# SMA-Q2_replacement_board_v2_1.net
KiCad netlist of a schematic drawn in EAGLE
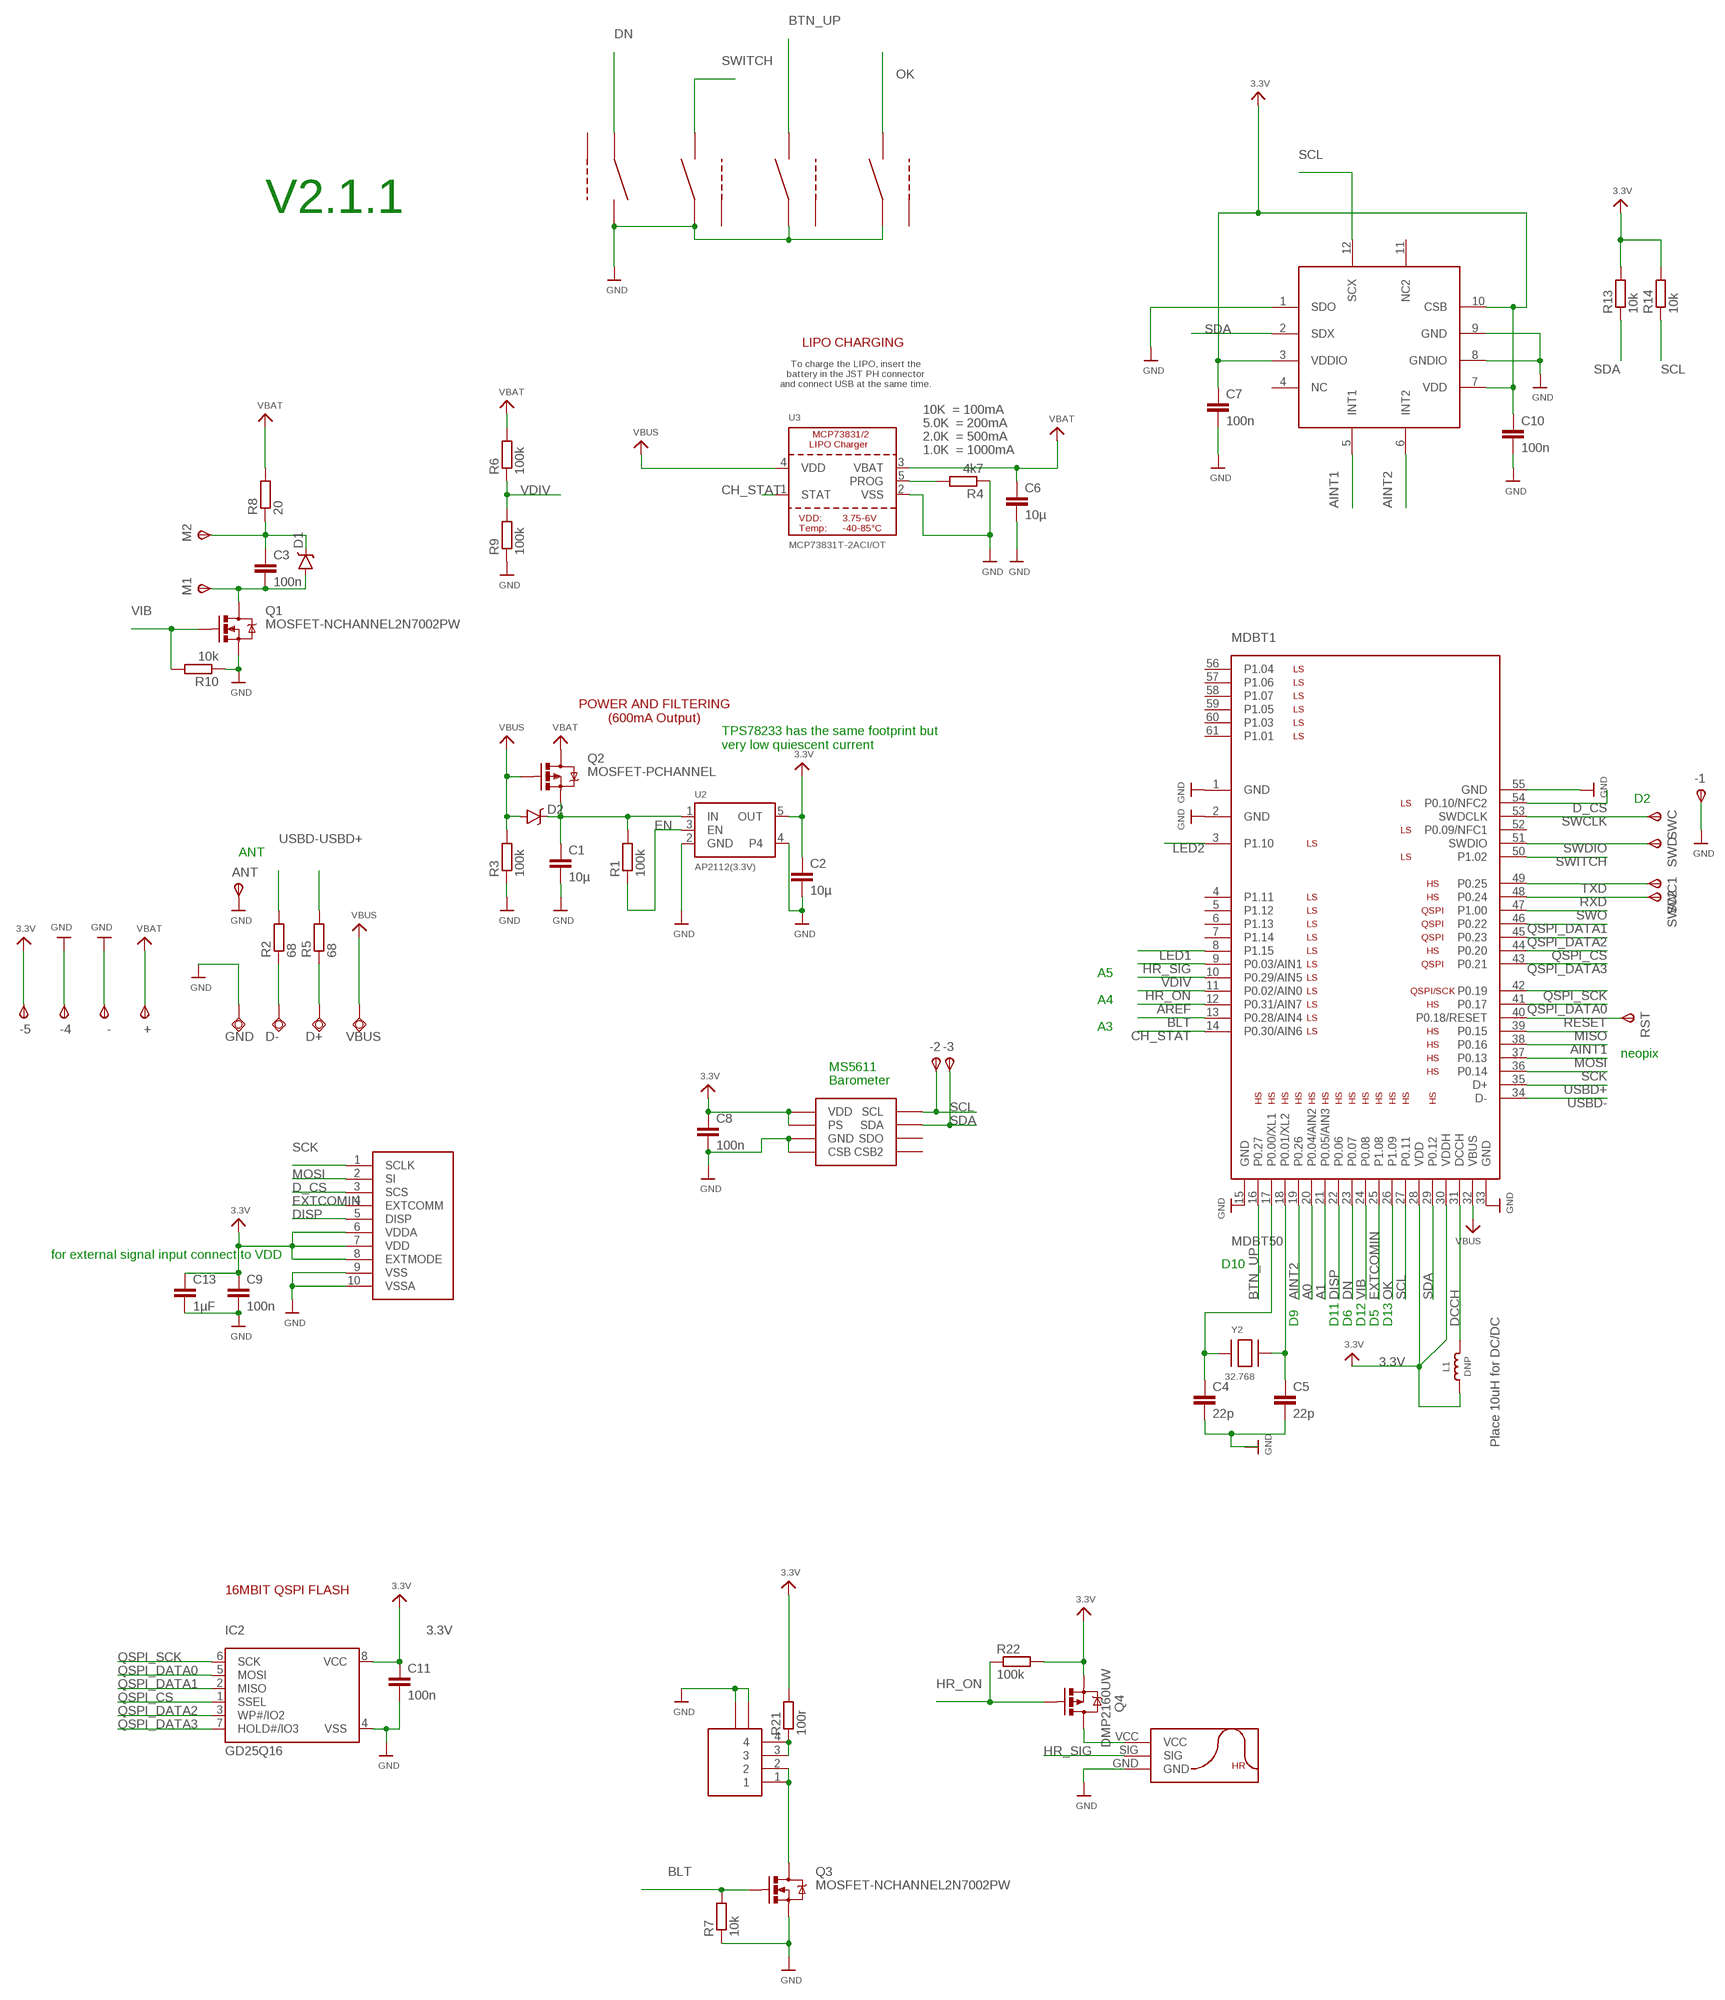
[diagram p0: schematic, sheet 1]

(export (version "E")
  (design (tool "Eeschema 10.0.6"))
  (components
    (comp (ref "+")
      (value "TPSTP09R")
      (footprint "eagle-import:TP09R")
      (libsource (lib "eagle-import") (part "TPSTP09R"))
    )
    (comp (ref "-")
      (value "TPSTP09R")
      (footprint "eagle-import:TP09R")
      (libsource (lib "eagle-import") (part "TPSTP09R"))
    )
    (comp (ref "-1")
      (value "TPSTP09R")
      (footprint "eagle-import:TP09R")
      (libsource (lib "eagle-import") (part "TPSTP09R"))
    )
    (comp (ref "-2")
      (value "TPSTP09R")
      (footprint "eagle-import:TP09R")
      (libsource (lib "eagle-import") (part "TPSTP09R"))
    )
    (comp (ref "-3")
      (value "TPSTP09R")
      (footprint "eagle-import:TP09R")
      (libsource (lib "eagle-import") (part "TPSTP09R"))
    )
    (comp (ref "-4")
      (value "TPSTP09R")
      (footprint "eagle-import:TP09R")
      (libsource (lib "eagle-import") (part "TPSTP09R"))
    )
    (comp (ref "-5")
      (value "TPSTP09R")
      (footprint "eagle-import:TP09R")
      (libsource (lib "eagle-import") (part "TPSTP09R"))
    )
    (comp (ref "ANT")
      (value "TPSTP19SQ")
      (footprint "eagle-import:TP19SQ")
      (libsource (lib "eagle-import") (part "TPSTP19SQ"))
    )
    (comp (ref "C1")
      (value "10µ")
      (footprint "eagle-import:C0603")
      (libsource (lib "eagle-import") (part "C-EUC0603"))
    )
    (comp (ref "C2")
      (value "10µ")
      (footprint "eagle-import:C0603")
      (libsource (lib "eagle-import") (part "C-EUC0603"))
    )
    (comp (ref "C3")
      (value "100n")
      (footprint "eagle-import:C0402")
      (libsource (lib "eagle-import") (part "C-EUC0402"))
    )
    (comp (ref "C4")
      (value "22p")
      (footprint "eagle-import:C0402")
      (libsource (lib "eagle-import") (part "C-EUC0402"))
    )
    (comp (ref "C5")
      (value "22p")
      (footprint "eagle-import:C0402")
      (libsource (lib "eagle-import") (part "C-EUC0402"))
    )
    (comp (ref "C6")
      (value "10µ")
      (footprint "eagle-import:C0603")
      (libsource (lib "eagle-import") (part "C-EUC0603"))
    )
    (comp (ref "C7")
      (value "100n")
      (footprint "eagle-import:C0402")
      (libsource (lib "eagle-import") (part "C-EUC0402"))
    )
    (comp (ref "C8")
      (value "100n")
      (footprint "eagle-import:C0402")
      (libsource (lib "eagle-import") (part "C-EUC0402"))
    )
    (comp (ref "C9")
      (value "100n")
      (footprint "eagle-import:C0402")
      (libsource (lib "eagle-import") (part "C-EUC0402"))
    )
    (comp (ref "C10")
      (value "100n")
      (footprint "eagle-import:C0402")
      (libsource (lib "eagle-import") (part "C-EUC0402"))
    )
    (comp (ref "C11")
      (value "100n")
      (footprint "eagle-import:C0402")
      (libsource (lib "eagle-import") (part "C-EUC0402"))
    )
    (comp (ref "C13")
      (value "1µF")
      (footprint "eagle-import:C0402")
      (libsource (lib "eagle-import") (part "C-EUC0402"))
    )
    (comp (ref "D+")
      (value "TPSQTP20R")
      (footprint "eagle-import:TP20R")
      (libsource (lib "eagle-import") (part "TPSQTP20R"))
    )
    (comp (ref "D-")
      (value "TPSQTP20R")
      (footprint "eagle-import:TP20R")
      (libsource (lib "eagle-import") (part "TPSQTP20R"))
    )
    (comp (ref "D1")
      (value "BAT20J")
      (footprint "eagle-import:SOD-323")
      (libsource (lib "eagle-import") (part "DIODE-SCHOTTKY-BAT20J"))
    )
    (comp (ref "D2")
      (value "BAT20J")
      (footprint "eagle-import:SOD-323")
      (libsource (lib "eagle-import") (part "DIODE-SCHOTTKY-BAT20J"))
    )
    (comp (ref "DWN")
      (value "LS12T2")
      (footprint "eagle-import:LS12T2")
      (libsource (lib "eagle-import") (part "LS12T2"))
    )
    (comp (ref "DWN1")
      (value "LS12T2")
      (footprint "eagle-import:LS12T2")
      (libsource (lib "eagle-import") (part "LS12T2"))
    )
    (comp (ref "DWN2")
      (value "LS12T2")
      (footprint "eagle-import:LS12T2")
      (libsource (lib "eagle-import") (part "LS12T2"))
    )
    (comp (ref "DWN3")
      (value "LS12T2")
      (footprint "eagle-import:LS12T2")
      (libsource (lib "eagle-import") (part "LS12T2"))
    )
    (comp (ref "GND")
      (value "TPSQTP20R")
      (footprint "eagle-import:TP20R")
      (libsource (lib "eagle-import") (part "TPSQTP20R"))
    )
    (comp (ref "IC2")
      (value "GD25Q16")
      (footprint "eagle-import:USON8")
      (libsource (lib "eagle-import") (part "SPIFLASH_8PINUX"))
    )
    (comp (ref "L1")
      (value "DNP")
      (footprint "eagle-import:_0805MP")
      (libsource (lib "eagle-import") (part "INDUCTOR_0805MP"))
    )
    (comp (ref "M1")
      (value "TPSTP09R")
      (footprint "eagle-import:TP09R")
      (libsource (lib "eagle-import") (part "TPSTP09R"))
    )
    (comp (ref "M2")
      (value "TPSTP09R")
      (footprint "eagle-import:TP09R")
      (libsource (lib "eagle-import") (part "TPSTP09R"))
    )
    (comp (ref "MDBT1")
      (value "MDBT50")
      (footprint "eagle-import:MDBT50")
      (libsource (lib "eagle-import") (part "MDBT50"))
    )
    (comp (ref "Q1")
      (value "MOSFET-NCHANNEL2N7002PW")
      (footprint "eagle-import:SOT323")
      (libsource (lib "eagle-import") (part "MOSFET-NCHANNEL2N7002PW"))
    )
    (comp (ref "Q2")
      (value "MOSFET-PCHANNEL")
      (footprint "eagle-import:SOT23-3")
      (libsource (lib "eagle-import") (part "MOSFET-PCHANNEL"))
    )
    (comp (ref "Q3")
      (value "MOSFET-NCHANNEL2N7002PW")
      (footprint "eagle-import:SOT323")
      (libsource (lib "eagle-import") (part "MOSFET-NCHANNEL2N7002PW"))
    )
    (comp (ref "Q4")
      (value "DMP2160UW")
      (footprint "eagle-import:SOT323")
      (libsource (lib "eagle-import") (part "MOSFET-P-CHANNEL-DMP2160UW"))
    )
    (comp (ref "R1")
      (value "100k")
      (footprint "eagle-import:R0402")
      (libsource (lib "eagle-import") (part "R-EU_R0402"))
    )
    (comp (ref "R2")
      (value "68")
      (footprint "eagle-import:R0402")
      (libsource (lib "eagle-import") (part "R-EU_R0402"))
    )
    (comp (ref "R3")
      (value "100k")
      (footprint "eagle-import:R0402")
      (libsource (lib "eagle-import") (part "R-EU_R0402"))
    )
    (comp (ref "R4")
      (value "4k7")
      (footprint "eagle-import:R0402")
      (libsource (lib "eagle-import") (part "R-EU_R0402"))
    )
    (comp (ref "R5")
      (value "68")
      (footprint "eagle-import:R0402")
      (libsource (lib "eagle-import") (part "R-EU_R0402"))
    )
    (comp (ref "R6")
      (value "100k")
      (footprint "eagle-import:R0402")
      (libsource (lib "eagle-import") (part "R-EU_R0402"))
    )
    (comp (ref "R7")
      (value "10k")
      (footprint "eagle-import:R0402")
      (libsource (lib "eagle-import") (part "R-EU_R0402"))
    )
    (comp (ref "R8")
      (value "20")
      (footprint "eagle-import:R0402")
      (libsource (lib "eagle-import") (part "R-EU_R0402"))
    )
    (comp (ref "R9")
      (value "100k")
      (footprint "eagle-import:R0402")
      (libsource (lib "eagle-import") (part "R-EU_R0402"))
    )
    (comp (ref "R10")
      (value "10k")
      (footprint "eagle-import:R0402")
      (libsource (lib "eagle-import") (part "R-EU_R0402"))
    )
    (comp (ref "R13")
      (value "10k")
      (footprint "eagle-import:R0402")
      (libsource (lib "eagle-import") (part "R-EU_R0402"))
    )
    (comp (ref "R14")
      (value "10k")
      (footprint "eagle-import:R0402")
      (libsource (lib "eagle-import") (part "R-EU_R0402"))
    )
    (comp (ref "R21")
      (value "100r")
      (footprint "eagle-import:R0402")
      (libsource (lib "eagle-import") (part "R-EU_R0402"))
    )
    (comp (ref "R22")
      (value "100k")
      (footprint "eagle-import:R0402")
      (libsource (lib "eagle-import") (part "R-EU_R0402"))
    )
    (comp (ref "RST")
      (value "TPSTP09R")
      (footprint "eagle-import:TP09R")
      (libsource (lib "eagle-import") (part "TPSTP09R"))
    )
    (comp (ref "SWC")
      (value "TPSTP09R")
      (footprint "eagle-import:TP09R")
      (libsource (lib "eagle-import") (part "TPSTP09R"))
    )
    (comp (ref "SWC1")
      (value "TPSTP09R")
      (footprint "eagle-import:TP09R")
      (libsource (lib "eagle-import") (part "TPSTP09R"))
    )
    (comp (ref "SWC2")
      (value "TPSTP09R")
      (footprint "eagle-import:TP09R")
      (libsource (lib "eagle-import") (part "TPSTP09R"))
    )
    (comp (ref "SWD")
      (value "TPSTP09R")
      (footprint "eagle-import:TP09R")
      (libsource (lib "eagle-import") (part "TPSTP09R"))
    )
    (comp (ref "U$2")
      (value "SHARP_MEM_DISP")
      (footprint "eagle-import:Y5BW")
      (libsource (lib "eagle-import") (part "SHARP_MEM_DISP"))
    )
    (comp (ref "U$6")
      (value "Y5B-4PIN")
      (footprint "eagle-import:Y5B-4PIN")
      (libsource (lib "eagle-import") (part "Y5B-4PIN"))
    )
    (comp (ref "U$7")
      (value "BMA400")
      (footprint "eagle-import:BMA400")
      (libsource (lib "eagle-import") (part "BMA400"))
    )
    (comp (ref "U$15")
      (value "MC5611")
      (footprint "eagle-import:MS5611")
      (libsource (lib "eagle-import") (part "MC5611"))
    )
    (comp (ref "U$45")
      (value "HR_PADS")
      (footprint "eagle-import:HR_PADS")
      (libsource (lib "eagle-import") (part "HR_PADS"))
    )
    (comp (ref "U2")
      (value "AP2112(3.3V)")
      (footprint "eagle-import:SOT23-5")
      (libsource (lib "eagle-import") (part "VREG_SOT23-5"))
    )
    (comp (ref "U3")
      (value "MCP73831T-2ACI/OT")
      (footprint "eagle-import:SOT23-5")
      (libsource (lib "eagle-import") (part "MCP73831/2"))
    )
    (comp (ref "VBUS")
      (value "TPSQTP20R")
      (footprint "eagle-import:TP20R")
      (libsource (lib "eagle-import") (part "TPSQTP20R"))
    )
    (comp (ref "Y2")
      (value "32.768")
      (footprint "eagle-import:XTAL3215")
      (libsource (lib "eagle-import") (part "XTAL-3.2X1.5"))
    )
  )
  (nets
    (net (code "1") (name "/A0") (class "Default")
      (node (ref "MDBT1") (pin "20") (pinfunction "P0.04/AIN2_20") (pintype "bidirectional"))
    )
    (net (code "2") (name "/A1") (class "Default")
      (node (ref "MDBT1") (pin "21") (pinfunction "P0.05/AIN3_21") (pintype "bidirectional"))
    )
    (net (code "3") (name "/AINT1") (class "Default")
      (node (ref "MDBT1") (pin "38") (pinfunction "P0.16_38") (pintype "bidirectional"))
      (node (ref "U$7") (pin "5") (pinfunction "INT1_5") (pintype "bidirectional"))
    )
    (net (code "4") (name "/AINT2") (class "Default")
      (node (ref "MDBT1") (pin "19") (pinfunction "P0.26_19") (pintype "bidirectional"))
      (node (ref "U$7") (pin "6") (pinfunction "INT2_6") (pintype "bidirectional"))
    )
    (net (code "5") (name "/AREF") (class "Default")
      (node (ref "MDBT1") (pin "12") (pinfunction "P0.31/AIN7_12") (pintype "bidirectional"))
    )
    (net (code "6") (name "/BLT") (class "Default")
      (node (ref "MDBT1") (pin "13") (pinfunction "P0.28/AIN4_13") (pintype "bidirectional"))
      (node (ref "Q3") (pin "1") (pinfunction "G_1") (pintype "passive"))
      (node (ref "R7") (pin "2") (pinfunction "2_2") (pintype "passive"))
    )
    (net (code "7") (name "/BTN_UP") (class "Default")
      (node (ref "DWN2") (pin "1") (pinfunction "1_1") (pintype "bidirectional"))
      (node (ref "MDBT1") (pin "16") (pinfunction "P0.27_16") (pintype "bidirectional"))
    )
    (net (code "8") (name "/CH_STAT") (class "Default")
      (node (ref "MDBT1") (pin "14") (pinfunction "P0.30/AIN6_14") (pintype "bidirectional"))
      (node (ref "U3") (pin "1") (pinfunction "STAT_1") (pintype "output"))
    )
    (net (code "9") (name "/DCCH") (class "Default")
      (node (ref "L1") (pin "2") (pinfunction "2_2") (pintype "passive"))
      (node (ref "MDBT1") (pin "31") (pinfunction "DCCH_31") (pintype "bidirectional"))
    )
    (net (code "10") (name "/DISP") (class "Default")
      (node (ref "MDBT1") (pin "22") (pinfunction "P0.06_22") (pintype "bidirectional"))
      (node (ref "U$2") (pin "5") (pinfunction "DISP_5") (pintype "bidirectional"))
    )
    (net (code "11") (name "/DN") (class "Default")
      (node (ref "DWN") (pin "2") (pinfunction "2_2") (pintype "bidirectional"))
      (node (ref "MDBT1") (pin "23") (pinfunction "P0.07_23") (pintype "bidirectional"))
    )
    (net (code "12") (name "/D_CS") (class "Default")
      (node (ref "MDBT1") (pin "54") (pinfunction "P0.10/NFC2_54") (pintype "bidirectional"))
      (node (ref "U$2") (pin "3") (pinfunction "SCS_3") (pintype "bidirectional"))
    )
    (net (code "13") (name "/EN") (class "Default")
      (node (ref "R1") (pin "1") (pinfunction "1_1") (pintype "passive"))
      (node (ref "U2") (pin "3") (pinfunction "EN_3") (pintype "input"))
    )
    (net (code "14") (name "/EXTCOMIN") (class "Default")
      (node (ref "MDBT1") (pin "25") (pinfunction "P1.08_25") (pintype "bidirectional"))
      (node (ref "U$2") (pin "4") (pinfunction "EXTCOMM_4") (pintype "bidirectional"))
    )
    (net (code "15") (name "/HR_ON") (class "Default")
      (node (ref "MDBT1") (pin "11") (pinfunction "P0.02/AIN0_11") (pintype "bidirectional"))
      (node (ref "Q4") (pin "1") (pinfunction "G_1") (pintype "passive"))
      (node (ref "R22") (pin "1") (pinfunction "1_1") (pintype "passive"))
    )
    (net (code "16") (name "/HR_SIG") (class "Default")
      (node (ref "MDBT1") (pin "9") (pinfunction "P0.03/AIN1_9") (pintype "bidirectional"))
      (node (ref "U$45") (pin "SIG") (pinfunction "SIG_SIG") (pintype "bidirectional"))
    )
    (net (code "17") (name "/LED1") (class "Default")
      (node (ref "MDBT1") (pin "8") (pinfunction "P1.15_8") (pintype "bidirectional"))
    )
    (net (code "18") (name "/LED2") (class "Default")
      (node (ref "MDBT1") (pin "3") (pinfunction "P1.10_3") (pintype "bidirectional"))
    )
    (net (code "19") (name "/MISO") (class "Default")
      (node (ref "MDBT1") (pin "39") (pinfunction "P0.15_39") (pintype "bidirectional"))
    )
    (net (code "20") (name "/MOSI") (class "Default")
      (node (ref "MDBT1") (pin "37") (pinfunction "P0.13_37") (pintype "bidirectional"))
      (node (ref "U$2") (pin "2") (pinfunction "SI_2") (pintype "bidirectional"))
    )
    (net (code "21") (name "/OK") (class "Default")
      (node (ref "DWN3") (pin "1") (pinfunction "1_1") (pintype "bidirectional"))
      (node (ref "MDBT1") (pin "26") (pinfunction "P1.09_26") (pintype "bidirectional"))
    )
    (net (code "22") (name "/QSPI_CS") (class "Default")
      (node (ref "IC2") (pin "1") (pinfunction "SSEL_1") (pintype "bidirectional"))
      (node (ref "MDBT1") (pin "44") (pinfunction "P0.20_44") (pintype "bidirectional"))
    )
    (net (code "23") (name "/QSPI_DATA0") (class "Default")
      (node (ref "IC2") (pin "5") (pinfunction "MOSI_5") (pintype "bidirectional"))
      (node (ref "MDBT1") (pin "41") (pinfunction "P0.17_41") (pintype "bidirectional"))
    )
    (net (code "24") (name "/QSPI_DATA1") (class "Default")
      (node (ref "IC2") (pin "2") (pinfunction "MISO_2") (pintype "bidirectional"))
      (node (ref "MDBT1") (pin "46") (pinfunction "P0.22_46") (pintype "bidirectional"))
    )
    (net (code "25") (name "/QSPI_DATA2") (class "Default")
      (node (ref "IC2") (pin "3") (pinfunction "WP#/IO2_3") (pintype "bidirectional"))
      (node (ref "MDBT1") (pin "45") (pinfunction "P0.23_45") (pintype "bidirectional"))
    )
    (net (code "26") (name "/QSPI_DATA3") (class "Default")
      (node (ref "IC2") (pin "7") (pinfunction "HOLD#/IO3_7") (pintype "bidirectional"))
      (node (ref "MDBT1") (pin "43") (pinfunction "P0.21_43") (pintype "bidirectional"))
    )
    (net (code "27") (name "/QSPI_SCK") (class "Default")
      (node (ref "IC2") (pin "6") (pinfunction "SCK_6") (pintype "bidirectional"))
      (node (ref "MDBT1") (pin "42") (pinfunction "P0.19_42") (pintype "bidirectional"))
    )
    (net (code "28") (name "/RESET") (class "Default")
      (node (ref "MDBT1") (pin "40") (pinfunction "P0.18/RESET_40") (pintype "bidirectional"))
      (node (ref "RST") (pin "TP") (pinfunction "PP_TP") (pintype "input"))
    )
    (net (code "29") (name "/RXD") (class "Default")
      (node (ref "MDBT1") (pin "48") (pinfunction "P0.24_48") (pintype "bidirectional"))
      (node (ref "SWC2") (pin "TP") (pinfunction "PP_TP") (pintype "input"))
    )
    (net (code "30") (name "/SCK") (class "Default")
      (node (ref "MDBT1") (pin "36") (pinfunction "P0.14_36") (pintype "bidirectional"))
      (node (ref "U$2") (pin "1") (pinfunction "SCLK_1") (pintype "bidirectional"))
    )
    (net (code "31") (name "/SCL") (class "Default")
      (node (ref "-2") (pin "TP") (pinfunction "PP_TP") (pintype "input"))
      (node (ref "MDBT1") (pin "27") (pinfunction "P0.11_27") (pintype "bidirectional"))
      (node (ref "R14") (pin "1") (pinfunction "1_1") (pintype "passive"))
      (node (ref "U$15") (pin "SCL") (pinfunction "SCL_SCL") (pintype "bidirectional"))
      (node (ref "U$7") (pin "12") (pinfunction "SCX_12") (pintype "bidirectional"))
    )
    (net (code "32") (name "/SDA") (class "Default")
      (node (ref "-3") (pin "TP") (pinfunction "PP_TP") (pintype "input"))
      (node (ref "MDBT1") (pin "29") (pinfunction "P0.12_29") (pintype "bidirectional"))
      (node (ref "R13") (pin "1") (pinfunction "1_1") (pintype "passive"))
      (node (ref "U$15") (pin "SDA") (pinfunction "SDA_SDA") (pintype "bidirectional"))
      (node (ref "U$7") (pin "2") (pinfunction "SDX_2") (pintype "bidirectional"))
    )
    (net (code "33") (name "/SWCLK") (class "Default")
      (node (ref "MDBT1") (pin "53") (pinfunction "SWDCLK_53") (pintype "bidirectional"))
      (node (ref "SWC") (pin "TP") (pinfunction "PP_TP") (pintype "input"))
    )
    (net (code "34") (name "/SWDIO") (class "Default")
      (node (ref "MDBT1") (pin "51") (pinfunction "SWDIO_51") (pintype "bidirectional"))
      (node (ref "SWD") (pin "TP") (pinfunction "PP_TP") (pintype "input"))
    )
    (net (code "35") (name "/SWITCH") (class "Default")
      (node (ref "DWN1") (pin "1") (pinfunction "1_1") (pintype "bidirectional"))
      (node (ref "MDBT1") (pin "50") (pinfunction "P1.02_50") (pintype "bidirectional"))
    )
    (net (code "36") (name "/SWO") (class "Default")
      (node (ref "MDBT1") (pin "47") (pinfunction "P1.00_47") (pintype "bidirectional"))
    )
    (net (code "37") (name "/TXD") (class "Default")
      (node (ref "MDBT1") (pin "49") (pinfunction "P0.25_49") (pintype "bidirectional"))
      (node (ref "SWC1") (pin "TP") (pinfunction "PP_TP") (pintype "input"))
    )
    (net (code "38") (name "/USBD+") (class "Default")
      (node (ref "MDBT1") (pin "35") (pinfunction "D+_35") (pintype "bidirectional"))
      (node (ref "R5") (pin "2") (pinfunction "2_2") (pintype "passive"))
    )
    (net (code "39") (name "/USBD-") (class "Default")
      (node (ref "MDBT1") (pin "34") (pinfunction "D-_34") (pintype "bidirectional"))
      (node (ref "R2") (pin "2") (pinfunction "2_2") (pintype "passive"))
    )
    (net (code "40") (name "/VDIV") (class "Default")
      (node (ref "MDBT1") (pin "10") (pinfunction "P0.29/AIN5_10") (pintype "bidirectional"))
      (node (ref "R6") (pin "1") (pinfunction "1_1") (pintype "passive"))
      (node (ref "R9") (pin "2") (pinfunction "2_2") (pintype "passive"))
    )
    (net (code "41") (name "/VIB") (class "Default")
      (node (ref "MDBT1") (pin "24") (pinfunction "P0.08_24") (pintype "bidirectional"))
      (node (ref "Q1") (pin "1") (pinfunction "G_1") (pintype "passive"))
      (node (ref "R10") (pin "2") (pinfunction "2_2") (pintype "passive"))
    )
    (net (code "42") (name "3.3V") (class "Default")
      (node (ref "-5") (pin "TP") (pinfunction "PP_TP") (pintype "input"))
      (node (ref "C10") (pin "1") (pinfunction "1_1") (pintype "passive"))
      (node (ref "C11") (pin "1") (pinfunction "1_1") (pintype "passive"))
      (node (ref "C13") (pin "1") (pinfunction "1_1") (pintype "passive"))
      (node (ref "C2") (pin "1") (pinfunction "1_1") (pintype "passive"))
      (node (ref "C7") (pin "1") (pinfunction "1_1") (pintype "passive"))
      (node (ref "C8") (pin "1") (pinfunction "1_1") (pintype "passive"))
      (node (ref "C9") (pin "1") (pinfunction "1_1") (pintype "passive"))
      (node (ref "IC2") (pin "8") (pinfunction "VCC_8") (pintype "bidirectional"))
      (node (ref "L1") (pin "1") (pinfunction "1_1") (pintype "passive"))
      (node (ref "MDBT1") (pin "28") (pinfunction "VDD_28") (pintype "bidirectional"))
      (node (ref "MDBT1") (pin "30") (pinfunction "VDDH_30") (pintype "bidirectional"))
      (node (ref "Q4") (pin "2") (pinfunction "S_2") (pintype "passive"))
      (node (ref "R13") (pin "2") (pinfunction "2_2") (pintype "passive"))
      (node (ref "R14") (pin "2") (pinfunction "2_2") (pintype "passive"))
      (node (ref "R21") (pin "2") (pinfunction "2_2") (pintype "passive"))
      (node (ref "R22") (pin "2") (pinfunction "2_2") (pintype "passive"))
      (node (ref "U$15") (pin "PS") (pinfunction "PS_PS") (pintype "bidirectional"))
      (node (ref "U$15") (pin "VDD") (pinfunction "VDD_VDD") (pintype "bidirectional"))
      (node (ref "U$2") (pin "6") (pinfunction "VDDA_6") (pintype "bidirectional"))
      (node (ref "U$2") (pin "7") (pinfunction "VDD_7") (pintype "bidirectional"))
      (node (ref "U$2") (pin "8") (pinfunction "EXTMODE_8") (pintype "bidirectional"))
      (node (ref "U$7") (pin "10") (pinfunction "CSB_10") (pintype "bidirectional"))
      (node (ref "U$7") (pin "3") (pinfunction "VDDIO_3") (pintype "bidirectional"))
      (node (ref "U$7") (pin "7") (pinfunction "VDD_7") (pintype "bidirectional"))
      (node (ref "U2") (pin "5") (pinfunction "OUT_5") (pintype "power_in"))
    )
    (net (code "43") (name "GND") (class "Default")
      (node (ref "-") (pin "TP") (pinfunction "PP_TP") (pintype "input"))
      (node (ref "-1") (pin "TP") (pinfunction "PP_TP") (pintype "input"))
      (node (ref "-4") (pin "TP") (pinfunction "PP_TP") (pintype "input"))
      (node (ref "ANT") (pin "TP") (pinfunction "PP_TP") (pintype "input"))
      (node (ref "C1") (pin "2") (pinfunction "2_2") (pintype "passive"))
      (node (ref "C10") (pin "2") (pinfunction "2_2") (pintype "passive"))
      (node (ref "C11") (pin "2") (pinfunction "2_2") (pintype "passive"))
      (node (ref "C13") (pin "2") (pinfunction "2_2") (pintype "passive"))
      (node (ref "C2") (pin "2") (pinfunction "2_2") (pintype "passive"))
      (node (ref "C4") (pin "2") (pinfunction "2_2") (pintype "passive"))
      (node (ref "C5") (pin "2") (pinfunction "2_2") (pintype "passive"))
      (node (ref "C6") (pin "2") (pinfunction "2_2") (pintype "passive"))
      (node (ref "C7") (pin "2") (pinfunction "2_2") (pintype "passive"))
      (node (ref "C8") (pin "2") (pinfunction "2_2") (pintype "passive"))
      (node (ref "C9") (pin "2") (pinfunction "2_2") (pintype "passive"))
      (node (ref "DWN") (pin "1") (pinfunction "1_1") (pintype "bidirectional"))
      (node (ref "DWN1") (pin "2") (pinfunction "2_2") (pintype "bidirectional"))
      (node (ref "DWN2") (pin "2") (pinfunction "2_2") (pintype "bidirectional"))
      (node (ref "DWN3") (pin "2") (pinfunction "2_2") (pintype "bidirectional"))
      (node (ref "GND") (pin "TP") (pinfunction "TP_TP") (pintype "input"))
      (node (ref "IC2") (pin "4") (pinfunction "VSS_4") (pintype "bidirectional"))
      (node (ref "MDBT1") (pin "1") (pinfunction "GND_1") (pintype "bidirectional"))
      (node (ref "MDBT1") (pin "15") (pinfunction "GND_15") (pintype "bidirectional"))
      (node (ref "MDBT1") (pin "2") (pinfunction "GND_2") (pintype "bidirectional"))
      (node (ref "MDBT1") (pin "33") (pinfunction "GND_33") (pintype "bidirectional"))
      (node (ref "MDBT1") (pin "55") (pinfunction "GND_55") (pintype "bidirectional"))
      (node (ref "Q1") (pin "2") (pinfunction "S_2") (pintype "passive"))
      (node (ref "Q3") (pin "2") (pinfunction "S_2") (pintype "passive"))
      (node (ref "R10") (pin "1") (pinfunction "1_1") (pintype "passive"))
      (node (ref "R3") (pin "1") (pinfunction "1_1") (pintype "passive"))
      (node (ref "R4") (pin "1") (pinfunction "1_1") (pintype "passive"))
      (node (ref "R7") (pin "1") (pinfunction "1_1") (pintype "passive"))
      (node (ref "R9") (pin "1") (pinfunction "1_1") (pintype "passive"))
      (node (ref "U$15") (pin "CSB") (pinfunction "CSB_CSB") (pintype "bidirectional"))
      (node (ref "U$15") (pin "GND") (pinfunction "GND_GND") (pintype "bidirectional"))
      (node (ref "U$2") (pin "10") (pinfunction "VSSA_10") (pintype "bidirectional"))
      (node (ref "U$2") (pin "9") (pinfunction "VSS_9") (pintype "bidirectional"))
      (node (ref "U$45") (pin "GND") (pinfunction "GND_GND") (pintype "bidirectional"))
      (node (ref "U$6") (pin "H1") (pinfunction "P$5_H1") (pintype "bidirectional"))
      (node (ref "U$6") (pin "H2") (pinfunction "P$6_H2") (pintype "bidirectional"))
      (node (ref "U$7") (pin "1") (pinfunction "SDO_1") (pintype "bidirectional"))
      (node (ref "U$7") (pin "8") (pinfunction "GNDIO_8") (pintype "bidirectional"))
      (node (ref "U$7") (pin "9") (pinfunction "GND_9") (pintype "bidirectional"))
      (node (ref "U2") (pin "2") (pinfunction "GND_2") (pintype "power_in"))
      (node (ref "U2") (pin "4") (pinfunction "P4_4") (pintype "bidirectional"))
      (node (ref "U3") (pin "2") (pinfunction "VSS_2") (pintype "power_in"))
    )
    (net (code "44") (name "Net-(D+-PadTP)") (class "Default")
      (node (ref "D+") (pin "TP") (pinfunction "TP_TP") (pintype "input"))
      (node (ref "R5") (pin "1") (pinfunction "1_1") (pintype "passive"))
    )
    (net (code "45") (name "Net-(D--PadTP)") (class "Default")
      (node (ref "D-") (pin "TP") (pinfunction "TP_TP") (pintype "input"))
      (node (ref "R2") (pin "1") (pinfunction "1_1") (pintype "passive"))
    )
    (net (code "46") (name "Net-(M1-PP)") (class "Default")
      (node (ref "C3") (pin "2") (pinfunction "2_2") (pintype "passive"))
      (node (ref "D1") (pin "A") (pinfunction "A_A") (pintype "passive"))
      (node (ref "M1") (pin "TP") (pinfunction "PP_TP") (pintype "input"))
      (node (ref "Q1") (pin "3") (pinfunction "D_3") (pintype "passive"))
    )
    (net (code "47") (name "Net-(M2-PP)") (class "Default")
      (node (ref "C3") (pin "1") (pinfunction "1_1") (pintype "passive"))
      (node (ref "D1") (pin "C") (pinfunction "C_C") (pintype "passive"))
      (node (ref "M2") (pin "TP") (pinfunction "PP_TP") (pintype "input"))
      (node (ref "R8") (pin "1") (pinfunction "1_1") (pintype "passive"))
    )
    (net (code "48") (name "Net-(MDBT1-P0.00{slash}XL1)") (class "Default")
      (node (ref "C4") (pin "1") (pinfunction "1_1") (pintype "passive"))
      (node (ref "MDBT1") (pin "17") (pinfunction "P0.00/XL1_17") (pintype "bidirectional"))
      (node (ref "Y2") (pin "P$1") (pinfunction "P$1_P$1") (pintype "bidirectional"))
    )
    (net (code "49") (name "Net-(MDBT1-P0.01{slash}XL2)") (class "Default")
      (node (ref "C5") (pin "1") (pinfunction "1_1") (pintype "passive"))
      (node (ref "MDBT1") (pin "18") (pinfunction "P0.01/XL2_18") (pintype "bidirectional"))
      (node (ref "Y2") (pin "P$2") (pinfunction "P$2_P$2") (pintype "bidirectional"))
    )
    (net (code "50") (name "Net-(Q2-S)") (class "Default")
      (node (ref "C1") (pin "1") (pinfunction "1_1") (pintype "passive"))
      (node (ref "D2") (pin "C") (pinfunction "C_C") (pintype "passive"))
      (node (ref "Q2") (pin "2") (pinfunction "S_2") (pintype "passive"))
      (node (ref "R1") (pin "2") (pinfunction "2_2") (pintype "passive"))
      (node (ref "U2") (pin "1") (pinfunction "IN_1") (pintype "power_in"))
    )
    (net (code "51") (name "Net-(Q3-D)") (class "Default")
      (node (ref "Q3") (pin "3") (pinfunction "D_3") (pintype "passive"))
      (node (ref "U$6") (pin "1") (pinfunction "1_1") (pintype "bidirectional"))
      (node (ref "U$6") (pin "2") (pinfunction "2_2") (pintype "bidirectional"))
    )
    (net (code "52") (name "Net-(Q4-D)") (class "Default")
      (node (ref "Q4") (pin "3") (pinfunction "D_3") (pintype "passive"))
      (node (ref "U$45") (pin "VCC") (pinfunction "VCC_VCC") (pintype "bidirectional"))
    )
    (net (code "53") (name "Net-(R21-Pad1)") (class "Default")
      (node (ref "R21") (pin "1") (pinfunction "1_1") (pintype "passive"))
      (node (ref "U$6") (pin "3") (pinfunction "3_3") (pintype "bidirectional"))
      (node (ref "U$6") (pin "4") (pinfunction "4_4") (pintype "bidirectional"))
    )
    (net (code "54") (name "Net-(U3-PROG)") (class "Default")
      (node (ref "R4") (pin "2") (pinfunction "2_2") (pintype "passive"))
      (node (ref "U3") (pin "5") (pinfunction "PROG_5") (pintype "input"))
    )
    (net (code "55") (name "VBAT") (class "Default")
      (node (ref "+") (pin "TP") (pinfunction "PP_TP") (pintype "input"))
      (node (ref "C6") (pin "1") (pinfunction "1_1") (pintype "passive"))
      (node (ref "Q2") (pin "3") (pinfunction "D_3") (pintype "passive"))
      (node (ref "R6") (pin "2") (pinfunction "2_2") (pintype "passive"))
      (node (ref "R8") (pin "2") (pinfunction "2_2") (pintype "passive"))
      (node (ref "U3") (pin "3") (pinfunction "VBAT_3") (pintype "power_in"))
    )
    (net (code "56") (name "VBUS") (class "Default")
      (node (ref "D2") (pin "A") (pinfunction "A_A") (pintype "passive"))
      (node (ref "MDBT1") (pin "32") (pinfunction "VBUS_32") (pintype "bidirectional"))
      (node (ref "Q2") (pin "1") (pinfunction "G_1") (pintype "passive"))
      (node (ref "R3") (pin "2") (pinfunction "2_2") (pintype "passive"))
      (node (ref "U3") (pin "4") (pinfunction "VDD_4") (pintype "power_in"))
      (node (ref "VBUS") (pin "TP") (pinfunction "TP_TP") (pintype "input"))
    )
    (net (code "57") (name "unconnected-(DWN-FRM-PadFRAME)") (class "Default")
      (node (ref "DWN") (pin "FRAME") (pinfunction "FRM_FRAME") (pintype "bidirectional"))
    )
    (net (code "58") (name "unconnected-(DWN1-FRM-PadFRAME)") (class "Default")
      (node (ref "DWN1") (pin "FRAME") (pinfunction "FRM_FRAME") (pintype "bidirectional"))
    )
    (net (code "59") (name "unconnected-(DWN2-FRM-PadFRAME)") (class "Default")
      (node (ref "DWN2") (pin "FRAME") (pinfunction "FRM_FRAME") (pintype "bidirectional"))
    )
    (net (code "60") (name "unconnected-(DWN3-FRM-PadFRAME)") (class "Default")
      (node (ref "DWN3") (pin "FRAME") (pinfunction "FRM_FRAME") (pintype "bidirectional"))
    )
    (net (code "61") (name "unconnected-(MDBT1-P0.09{slash}NFC1-Pad52)") (class "Default")
      (node (ref "MDBT1") (pin "52") (pinfunction "P0.09/NFC1_52") (pintype "bidirectional"))
    )
    (net (code "62") (name "unconnected-(MDBT1-P1.01-Pad61)") (class "Default")
      (node (ref "MDBT1") (pin "61") (pinfunction "P1.01_61") (pintype "bidirectional"))
    )
    (net (code "63") (name "unconnected-(MDBT1-P1.03-Pad60)") (class "Default")
      (node (ref "MDBT1") (pin "60") (pinfunction "P1.03_60") (pintype "bidirectional"))
    )
    (net (code "64") (name "unconnected-(MDBT1-P1.04-Pad56)") (class "Default")
      (node (ref "MDBT1") (pin "56") (pinfunction "P1.04_56") (pintype "bidirectional"))
    )
    (net (code "65") (name "unconnected-(MDBT1-P1.05-Pad59)") (class "Default")
      (node (ref "MDBT1") (pin "59") (pinfunction "P1.05_59") (pintype "bidirectional"))
    )
    (net (code "66") (name "unconnected-(MDBT1-P1.06-Pad57)") (class "Default")
      (node (ref "MDBT1") (pin "57") (pinfunction "P1.06_57") (pintype "bidirectional"))
    )
    (net (code "67") (name "unconnected-(MDBT1-P1.07-Pad58)") (class "Default")
      (node (ref "MDBT1") (pin "58") (pinfunction "P1.07_58") (pintype "bidirectional"))
    )
    (net (code "68") (name "unconnected-(MDBT1-P1.11-Pad4)") (class "Default")
      (node (ref "MDBT1") (pin "4") (pinfunction "P1.11_4") (pintype "bidirectional"))
    )
    (net (code "69") (name "unconnected-(MDBT1-P1.12-Pad5)") (class "Default")
      (node (ref "MDBT1") (pin "5") (pinfunction "P1.12_5") (pintype "bidirectional"))
    )
    (net (code "70") (name "unconnected-(MDBT1-P1.13-Pad6)") (class "Default")
      (node (ref "MDBT1") (pin "6") (pinfunction "P1.13_6") (pintype "bidirectional"))
    )
    (net (code "71") (name "unconnected-(MDBT1-P1.14-Pad7)") (class "Default")
      (node (ref "MDBT1") (pin "7") (pinfunction "P1.14_7") (pintype "bidirectional"))
    )
    (net (code "72") (name "unconnected-(U$7-NC-Pad4)") (class "Default")
      (node (ref "U$7") (pin "4") (pinfunction "NC_4") (pintype "bidirectional"))
    )
    (net (code "73") (name "unconnected-(U$7-NC2-Pad11)") (class "Default")
      (node (ref "U$7") (pin "11") (pinfunction "NC2_11") (pintype "bidirectional"))
    )
    (net (code "74") (name "unconnected-(U$15-PadCSB2)") (class "Default")
      (node (ref "U$15") (pin "CSB2") (pinfunction "CSB2_CSB2") (pintype "bidirectional"))
    )
    (net (code "75") (name "unconnected-(U$15-PadSDO)") (class "Default")
      (node (ref "U$15") (pin "SDO") (pinfunction "SDO_SDO") (pintype "bidirectional"))
    )
  )
)
